# IMU_REV_E.net
KiCad netlist of a schematic drawn in Altium Designer
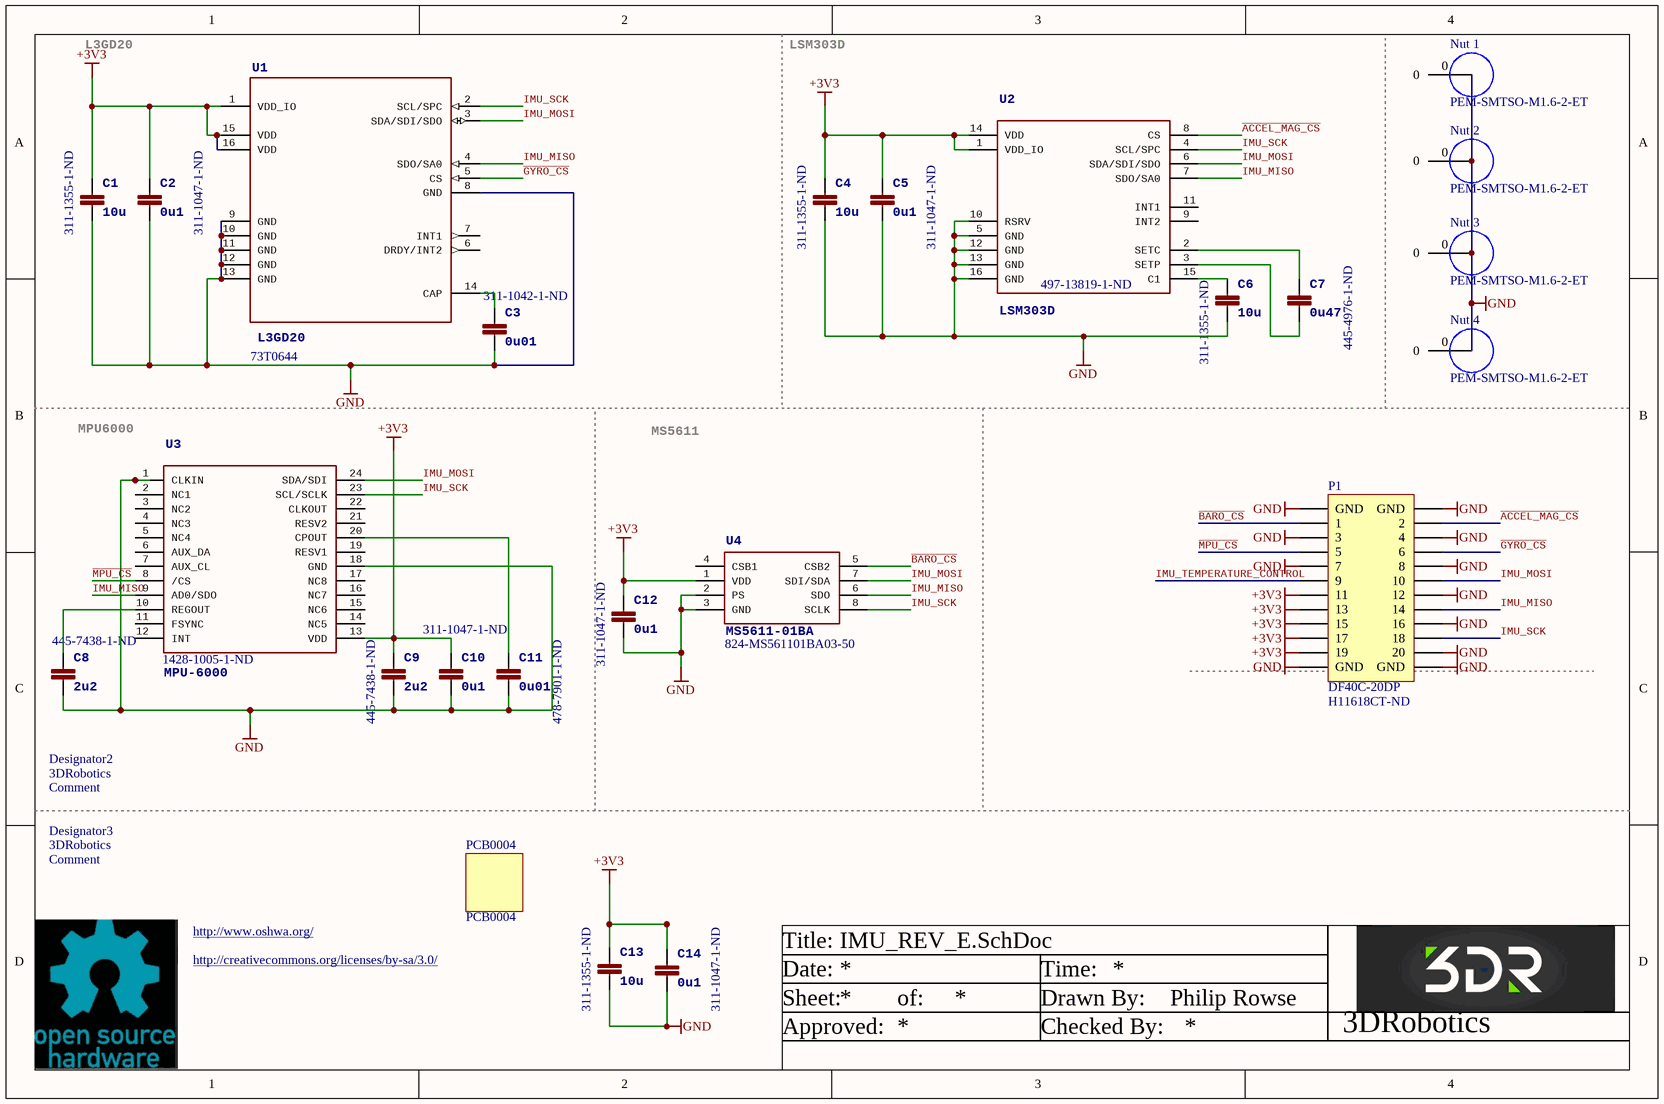
[diagram p0: IMU_REV_E.SchDoc]

(export (version "E")
  (design (tool "Eeschema 10.0.6"))
  (components
    (comp (ref "C1")
      (value "10u")
      (footprint "0805-CAP")
      (description "Capacitor, 10uF, 10V, Y5V, 0805, Ceramic")
      (fields
        (field (name "PARTNO") "CC0805ZKY5V6BB106")
        (field (name "SUPPLIER PART NUMBER 1") "311-1355-1-ND")
        (field (name "3DR_PARTNO") "ECM0713")
      )
      (libsource (lib "lib_pixhawk") (part "CAPACITOR-0805"))
    )
    (comp (ref "C2")
      (value "0u1")
      (footprint "0402-CAP")
      (description "Capacitor, 0.1uF, 16V, Y5V, 0402, Ceramic")
      (fields
        (field (name "PARTNO") "CC0402ZRY5V7BB104")
        (field (name "SUPPLIER PART NUMBER 1") "311-1047-1-ND")
        (field (name "3DR_PARTNO") "ECM0700")
      )
      (libsource (lib "lib_pixhawk") (part "CAPACITOR-0402"))
    )
    (comp (ref "C3")
      (value "0u01")
      (footprint "0402-CAP")
      (description "Capacitor, 10000pF, 16V, 10%, X7R, 0402, Ceramic")
      (fields
        (field (name "PARTNO") "CC0402KRX7R7BB103")
        (field (name "SUPPLIER PART NUMBER 1") "311-1042-1-ND")
        (field (name "3DR_PARTNO") "ECM0711")
      )
      (libsource (lib "lib_pixhawk") (part "CAPACITOR-0402"))
    )
    (comp (ref "C4")
      (value "10u")
      (footprint "0805-CAP")
      (description "Capacitor, 10uF, 10V, Y5V, 0805, Ceramic")
      (fields
        (field (name "PARTNO") "CC0805ZKY5V6BB106")
        (field (name "SUPPLIER PART NUMBER 1") "311-1355-1-ND")
        (field (name "3DR_PARTNO") "ECM0713")
      )
      (libsource (lib "lib_pixhawk") (part "CAPACITOR-0805"))
    )
    (comp (ref "C5")
      (value "0u1")
      (footprint "0402-CAP")
      (description "Capacitor, 0.1uF, 16V, Y5V, 0402, Ceramic")
      (fields
        (field (name "PARTNO") "CC0402ZRY5V7BB104")
        (field (name "SUPPLIER PART NUMBER 1") "311-1047-1-ND")
        (field (name "3DR_PARTNO") "ECM0700")
      )
      (libsource (lib "lib_pixhawk") (part "CAPACITOR-0402"))
    )
    (comp (ref "C6")
      (value "10u")
      (footprint "0805-CAP")
      (description "Capacitor, 10uF, 10V, Y5V, 0805, Ceramic")
      (fields
        (field (name "PARTNO") "CC0805ZKY5V6BB106")
        (field (name "SUPPLIER PART NUMBER 1") "311-1355-1-ND")
        (field (name "3DR_PARTNO") "ECM0713")
      )
      (libsource (lib "lib_pixhawk") (part "CAPACITOR-0805"))
    )
    (comp (ref "C7")
      (value "0u47")
      (footprint "0402-CAP")
      (description "Capacitor,  0.47uF, 16V, 10%, X5R, 0402, Ceramic")
      (fields
        (field (name "PARTNO") "C1005X5R1C474K050BC")
        (field (name "SUPPLIER PART NUMBER 1") "445-4976-1-ND")
        (field (name "3DR_PARTNO") "ECM0704")
      )
      (libsource (lib "lib_pixhawk") (part "CAPACITOR-0402"))
    )
    (comp (ref "C8")
      (value "2u2")
      (footprint "0603-CAP")
      (description "Capacitor, 2.2uF, 16V, 10%, X6S, 0603, Ceramic")
      (fields
        (field (name "PARTNO") "C1608X6S1C225K080AC")
        (field (name "SUPPLIER PART NUMBER 1") "445-7438-1-ND")
        (field (name "3DR_PARTNO") "ECM0619")
      )
      (libsource (lib "lib_pixhawk") (part "CAPACITOR-0603"))
    )
    (comp (ref "C9")
      (value "2u2")
      (footprint "0603-CAP")
      (description "Capacitor, 2.2uF, 16V, 10%, X6S, 0603, Ceramic")
      (fields
        (field (name "PARTNO") "C1608X6S1C225K080AC")
        (field (name "SUPPLIER PART NUMBER 1") "445-7438-1-ND")
        (field (name "3DR_PARTNO") "ECM0619")
      )
      (libsource (lib "lib_pixhawk") (part "CAPACITOR-0603"))
    )
    (comp (ref "C10")
      (value "0u1")
      (footprint "0402-CAP")
      (description "Capacitor, 0.1uF, 16V, Y5V, 0402, Ceramic")
      (fields
        (field (name "PARTNO") "CC0402ZRY5V7BB104")
        (field (name "SUPPLIER PART NUMBER 1") "311-1047-1-ND")
        (field (name "3DR_PARTNO") "ECM0700")
      )
      (libsource (lib "lib_pixhawk") (part "CAPACITOR-0402"))
    )
    (comp (ref "C11")
      (value "0u01")
      (footprint "0603-CAP")
      (description "Capacitor, 10000pF, 25V, 5%, X7R, 0603, Ceramic")
      (fields
        (field (name "PARTNO") "06033C103JAT2A")
        (field (name "SUPPLIER PART NUMBER 1") "478-7901-1-ND")
        (field (name "3DR_PARTNO") "ECM0620")
      )
      (libsource (lib "lib_pixhawk") (part "CAPACITOR-0603"))
    )
    (comp (ref "C12")
      (value "0u1")
      (footprint "0402-CAP")
      (description "Capacitor, 0.1uF, 16V, Y5V, 0402, Ceramic")
      (fields
        (field (name "PARTNO") "CC0402ZRY5V7BB104")
        (field (name "SUPPLIER PART NUMBER 1") "311-1047-1-ND")
        (field (name "3DR_PARTNO") "ECM0700")
      )
      (libsource (lib "lib_pixhawk") (part "CAPACITOR-0402"))
    )
    (comp (ref "C13")
      (value "10u")
      (footprint "0805-CAP")
      (description "Capacitor, 10uF, 10V, Y5V, 0805, Ceramic")
      (fields
        (field (name "PARTNO") "CC0805ZKY5V6BB106")
        (field (name "SUPPLIER PART NUMBER 1") "311-1355-1-ND")
        (field (name "3DR_PARTNO") "ECM0713")
      )
      (libsource (lib "lib_pixhawk") (part "CAPACITOR-0805"))
    )
    (comp (ref "C14")
      (value "0u1")
      (footprint "0402-CAP")
      (description "Capacitor, 0.1uF, 16V, Y5V, 0402, Ceramic")
      (fields
        (field (name "PARTNO") "CC0402ZRY5V7BB104")
        (field (name "SUPPLIER PART NUMBER 1") "311-1047-1-ND")
        (field (name "3DR_PARTNO") "ECM0700")
      )
      (libsource (lib "lib_pixhawk") (part "CAPACITOR-0402"))
    )
    (comp (ref "Designator2")
      (value "Comment")
      (footprint "3DR_SMALL")
      (fields (field (name "PARTNO") "DO NOT FIT"))
      (libsource (lib "lib_pixhawk") (part "3DR-Logo Large"))
    )
    (comp (ref "Designator3")
      (value "Comment")
      (footprint "3DR_SMALL")
      (fields (field (name "PARTNO") "DO NOT FIT"))
      (libsource (lib "lib_pixhawk") (part "3DR-Logo Large"))
    )
    (comp (ref "Nut 1")
      (value "PEM-SMTSO-M1.6-2-ET")
      (footprint "PEM-SMTSO-M1.6-2-ET")
      (description "Fastener, M1.6x2mm, SMTSO, Carbon Steel")
      (fields (field (name "3DR_PARTNO") "PRT0438"))
      (libsource (lib "pixhawk2") (part "PEM-SMTSO-M1.6-2-ET"))
    )
    (comp (ref "Nut 2")
      (value "PEM-SMTSO-M1.6-2-ET")
      (footprint "PEM-SMTSO-M1.6-2-ET")
      (description "Fastener, M1.6x2mm, SMTSO, Carbon Steel")
      (fields (field (name "3DR_PARTNO") "PRT0438"))
      (libsource (lib "pixhawk2") (part "PEM-SMTSO-M1.6-2-ET"))
    )
    (comp (ref "Nut 3")
      (value "PEM-SMTSO-M1.6-2-ET")
      (footprint "PEM-SMTSO-M1.6-2-ET")
      (description "Fastener, M1.6x2mm, SMTSO, Carbon Steel")
      (fields (field (name "3DR_PARTNO") "PRT0438"))
      (libsource (lib "pixhawk2") (part "PEM-SMTSO-M1.6-2-ET"))
    )
    (comp (ref "Nut 4")
      (value "PEM-SMTSO-M1.6-2-ET")
      (footprint "PEM-SMTSO-M1.6-2-ET")
      (description "Fastener, M1.6x2mm, SMTSO, Carbon Steel")
      (fields (field (name "3DR_PARTNO") "PRT0438"))
      (libsource (lib "pixhawk2") (part "PEM-SMTSO-M1.6-2-ET"))
    )
    (comp (ref "P1")
      (value "DF40C-20DP")
      (footprint "DF40C-20-DP")
      (description "Connector, HDR, 20Pos, 0.4mm, SMD, GOLD")
      (fields
        (field (name "SUPPLIER PART NUMBER 1") "H11618CT-ND")
        (field (name "3DR_PARTNO") "ECM0510")
        (field (name "PUBLISHER") "Altium Limited")
      )
      (libsource (lib "pixhawk2") (part "DF40C-20DP"))
    )
    (comp (ref "PCB0004")
      (value "PCB0004")
      (description "IMU PCB")
      (libsource (lib "lib_pixhawk") (part "PCB_0004"))
    )
    (comp (ref "U1")
      (value "L3GD20")
      (footprint "L3GD20")
      (description "Sensor, Low-power, Three-axis, Angular rate")
      (fields (field (name "SUPPLIER PART NUMBER 1") "73T0644") (field (name "3DR_PARTNO") "ECM0827"))
      (libsource (lib "pixhawk2") (part "L3GD20"))
    )
    (comp (ref "U2")
      (value "LSM303D")
      (footprint "LSM303D")
      (description "Module, 3D Accelerometer, 3D Magnetometer")
      (fields (field (name "SUPPLIER PART NUMBER 1") "497-13819-1-ND") (field (name "3DR_PARTNO") "ECM0828"))
      (libsource (lib "pixhawk2") (part "LSM303D"))
    )
    (comp (ref "U3")
      (value "MPU-6000")
      (footprint "QFN-24")
      (description "3 Axis Accel, 3Axis Gyro")
      (fields (field (name "SUPPLIER PART NUMBER 1") "1428-1005-1-ND") (field (name "3DR_PARTNO") "ECM0834"))
      (libsource (lib "pixhawk2") (part "MPU-6000"))
    )
    (comp (ref "U4")
      (value "MS5611-01BA")
      (footprint "MS5611-01BA")
      (description "Board, Digital pressure sensor I2C/SPI")
      (fields
        (field (name "SUPPLIER PART NUMBER 1") "824-MS561101BA03-50")
        (field (name "3DR_PARTNO") "ECM0835")
      )
      (libsource (lib "pixhawk2") (part "MS5611-01BA"))
    )
  )
  (nets
    (net (code "1") (name "+3V3") (class "Default")
      (node (ref "C1") (pin "P$1") (pinfunction "1_P$1") (pintype "passive"))
      (node (ref "C10") (pin "P$1") (pinfunction "1_P$1") (pintype "passive"))
      (node (ref "C12") (pin "P$1") (pinfunction "1_P$1") (pintype "passive"))
      (node (ref "C13") (pin "P$1") (pinfunction "1_P$1") (pintype "passive"))
      (node (ref "C14") (pin "P$1") (pinfunction "1_P$1") (pintype "passive"))
      (node (ref "C2") (pin "P$1") (pinfunction "1_P$1") (pintype "passive"))
      (node (ref "C4") (pin "P$1") (pinfunction "1_P$1") (pintype "passive"))
      (node (ref "C5") (pin "P$1") (pinfunction "1_P$1") (pintype "passive"))
      (node (ref "C9") (pin "P$1") (pinfunction "1_P$1") (pintype "passive"))
      (node (ref "P1") (pin "11") (pinfunction "11_11") (pintype "passive"))
      (node (ref "P1") (pin "13") (pinfunction "13_13") (pintype "passive"))
      (node (ref "P1") (pin "15") (pinfunction "15_15") (pintype "passive"))
      (node (ref "P1") (pin "17") (pinfunction "17_17") (pintype "passive"))
      (node (ref "P1") (pin "19") (pinfunction "19_19") (pintype "passive"))
      (node (ref "U1") (pin "1") (pinfunction "VDD_IO_1") (pintype "power_in"))
      (node (ref "U1") (pin "15") (pinfunction "VDD_15") (pintype "power_in"))
      (node (ref "U1") (pin "16") (pinfunction "VDD_16") (pintype "power_in"))
      (node (ref "U2") (pin "1") (pinfunction "VDD_IO_1") (pintype "passive"))
      (node (ref "U2") (pin "14") (pinfunction "VDD_14") (pintype "passive"))
      (node (ref "U3") (pin "13") (pinfunction "VDD_13") (pintype "passive"))
      (node (ref "U4") (pin "1") (pinfunction "VDD_1") (pintype "passive"))
    )
    (net (code "2") (name "/IMU_MISO") (class "Default")
      (node (ref "P1") (pin "14") (pinfunction "14_14") (pintype "passive"))
      (node (ref "U1") (pin "4") (pinfunction "SDO/SA0_4") (pintype "input"))
      (node (ref "U2") (pin "7") (pinfunction "SDO/SA0_7") (pintype "passive"))
      (node (ref "U3") (pin "9") (pinfunction "AD0/SDO_9") (pintype "passive"))
      (node (ref "U4") (pin "6") (pinfunction "SDO_6") (pintype "passive"))
    )
    (net (code "3") (name "/IMU_MOSI") (class "Default")
      (node (ref "P1") (pin "10") (pinfunction "10_10") (pintype "passive"))
      (node (ref "U1") (pin "3") (pinfunction "SDA/SDI/SDO_3") (pintype "bidirectional"))
      (node (ref "U2") (pin "6") (pinfunction "SDA/SDI/SDO_6") (pintype "passive"))
      (node (ref "U3") (pin "24") (pinfunction "SDA/SDI_24") (pintype "passive"))
      (node (ref "U4") (pin "7") (pinfunction "SDI/SDA_7") (pintype "passive"))
    )
    (net (code "4") (name "/IMU_SCK") (class "Default")
      (node (ref "P1") (pin "18") (pinfunction "18_18") (pintype "passive"))
      (node (ref "U1") (pin "2") (pinfunction "SCL/SPC_2") (pintype "input"))
      (node (ref "U2") (pin "4") (pinfunction "SCL/SPC_4") (pintype "passive"))
      (node (ref "U3") (pin "23") (pinfunction "SCL/SCLK_23") (pintype "passive"))
      (node (ref "U4") (pin "8") (pinfunction "SCLK_8") (pintype "passive"))
    )
    (net (code "5") (name "/IMU_TEMPERATURE_CONTROL") (class "Default")
      (node (ref "P1") (pin "9") (pinfunction "9_9") (pintype "passive"))
    )
    (net (code "6") (name "/~{ACCEL_MAG_CS}") (class "Default")
      (node (ref "P1") (pin "2") (pinfunction "2_2") (pintype "passive"))
      (node (ref "U2") (pin "8") (pinfunction "CS_8") (pintype "passive"))
    )
    (net (code "7") (name "/~{BARO_CS}") (class "Default")
      (node (ref "P1") (pin "1") (pinfunction "1_1") (pintype "passive"))
      (node (ref "U4") (pin "5") (pinfunction "CSB2_5") (pintype "passive"))
    )
    (net (code "8") (name "/~{GYRO_CS}") (class "Default")
      (node (ref "P1") (pin "6") (pinfunction "6_6") (pintype "passive"))
      (node (ref "U1") (pin "5") (pinfunction "CS_5") (pintype "input"))
    )
    (net (code "9") (name "/~{MPU_CS}") (class "Default")
      (node (ref "P1") (pin "5") (pinfunction "5_5") (pintype "passive"))
      (node (ref "U3") (pin "8") (pinfunction "/CS_8") (pintype "passive"))
    )
    (net (code "10") (name "GND") (class "Default")
      (node (ref "C1") (pin "P$2") (pinfunction "2_P$2") (pintype "passive"))
      (node (ref "C10") (pin "P$2") (pinfunction "2_P$2") (pintype "passive"))
      (node (ref "C11") (pin "P$2") (pinfunction "2_P$2") (pintype "passive"))
      (node (ref "C12") (pin "P$2") (pinfunction "2_P$2") (pintype "passive"))
      (node (ref "C13") (pin "P$2") (pinfunction "2_P$2") (pintype "passive"))
      (node (ref "C14") (pin "P$2") (pinfunction "2_P$2") (pintype "passive"))
      (node (ref "C2") (pin "P$2") (pinfunction "2_P$2") (pintype "passive"))
      (node (ref "C3") (pin "P$2") (pinfunction "2_P$2") (pintype "passive"))
      (node (ref "C4") (pin "P$2") (pinfunction "2_P$2") (pintype "passive"))
      (node (ref "C5") (pin "P$2") (pinfunction "2_P$2") (pintype "passive"))
      (node (ref "C6") (pin "P$2") (pinfunction "2_P$2") (pintype "passive"))
      (node (ref "C8") (pin "P$2") (pinfunction "2_P$2") (pintype "passive"))
      (node (ref "C9") (pin "P$2") (pinfunction "2_P$2") (pintype "passive"))
      (node (ref "Nut 1") (pin "0") (pinfunction "0_0") (pintype "passive"))
      (node (ref "Nut 2") (pin "0") (pinfunction "0_0") (pintype "passive"))
      (node (ref "Nut 3") (pin "0") (pinfunction "0_0") (pintype "passive"))
      (node (ref "Nut 4") (pin "0") (pinfunction "0_0") (pintype "passive"))
      (node (ref "P1") (pin "12") (pinfunction "12_12") (pintype "passive"))
      (node (ref "P1") (pin "16") (pinfunction "16_16") (pintype "passive"))
      (node (ref "P1") (pin "20") (pinfunction "20_20") (pintype "passive"))
      (node (ref "P1") (pin "21") (pinfunction "GND_21") (pintype "passive"))
      (node (ref "P1") (pin "22") (pinfunction "GND_22") (pintype "passive"))
      (node (ref "P1") (pin "23") (pinfunction "GND_23") (pintype "passive"))
      (node (ref "P1") (pin "24") (pinfunction "GND_24") (pintype "passive"))
      (node (ref "P1") (pin "3") (pinfunction "3_3") (pintype "passive"))
      (node (ref "P1") (pin "4") (pinfunction "4_4") (pintype "passive"))
      (node (ref "P1") (pin "7") (pinfunction "7_7") (pintype "passive"))
      (node (ref "P1") (pin "8") (pinfunction "8_8") (pintype "passive"))
      (node (ref "U1") (pin "10") (pinfunction "GND_10") (pintype "power_in"))
      (node (ref "U1") (pin "11") (pinfunction "GND_11") (pintype "power_in"))
      (node (ref "U1") (pin "12") (pinfunction "GND_12") (pintype "power_in"))
      (node (ref "U1") (pin "13") (pinfunction "GND_13") (pintype "power_in"))
      (node (ref "U1") (pin "8") (pinfunction "GND_8") (pintype "power_in"))
      (node (ref "U1") (pin "9") (pinfunction "GND_9") (pintype "power_in"))
      (node (ref "U2") (pin "10") (pinfunction "RSRV_10") (pintype "passive"))
      (node (ref "U2") (pin "12") (pinfunction "GND_12") (pintype "passive"))
      (node (ref "U2") (pin "13") (pinfunction "GND_13") (pintype "passive"))
      (node (ref "U2") (pin "16") (pinfunction "GND_16") (pintype "passive"))
      (node (ref "U2") (pin "5") (pinfunction "GND_5") (pintype "passive"))
      (node (ref "U3") (pin "1") (pinfunction "CLKIN_1") (pintype "passive"))
      (node (ref "U3") (pin "18") (pinfunction "GND_18") (pintype "passive"))
      (node (ref "U4") (pin "2") (pinfunction "PS_2") (pintype "passive"))
      (node (ref "U4") (pin "3") (pinfunction "GND_3") (pintype "passive"))
    )
    (net (code "11") (name "Net-(C3-1)") (class "Default")
      (node (ref "C3") (pin "P$1") (pinfunction "1_P$1") (pintype "passive"))
      (node (ref "U1") (pin "14") (pinfunction "CAP_14") (pintype "passive"))
    )
    (net (code "12") (name "Net-(C6-1)") (class "Default")
      (node (ref "C6") (pin "P$1") (pinfunction "1_P$1") (pintype "passive"))
      (node (ref "U2") (pin "15") (pinfunction "C1_15") (pintype "passive"))
    )
    (net (code "13") (name "Net-(C7-1)") (class "Default")
      (node (ref "C7") (pin "P$1") (pinfunction "1_P$1") (pintype "passive"))
      (node (ref "U2") (pin "2") (pinfunction "SETC_2") (pintype "passive"))
    )
    (net (code "14") (name "Net-(C7-2)") (class "Default")
      (node (ref "C7") (pin "P$2") (pinfunction "2_P$2") (pintype "passive"))
      (node (ref "U2") (pin "3") (pinfunction "SETP_3") (pintype "passive"))
    )
    (net (code "15") (name "Net-(C8-1)") (class "Default")
      (node (ref "C8") (pin "P$1") (pinfunction "1_P$1") (pintype "passive"))
      (node (ref "U3") (pin "10") (pinfunction "REGOUT_10") (pintype "passive"))
    )
    (net (code "16") (name "Net-(C11-1)") (class "Default")
      (node (ref "C11") (pin "P$1") (pinfunction "1_P$1") (pintype "passive"))
      (node (ref "U3") (pin "20") (pinfunction "CPOUT_20") (pintype "passive"))
    )
    (net (code "17") (name "unconnected-(U1-DRDY{slash}INT2-Pad6)") (class "Default")
      (node (ref "U1") (pin "6") (pinfunction "DRDY/INT2_6") (pintype "output"))
    )
    (net (code "18") (name "unconnected-(U1-INT1-Pad7)") (class "Default")
      (node (ref "U1") (pin "7") (pinfunction "INT1_7") (pintype "output"))
    )
    (net (code "19") (name "unconnected-(U2-INT1-Pad11)") (class "Default")
      (node (ref "U2") (pin "11") (pinfunction "INT1_11") (pintype "passive"))
    )
    (net (code "20") (name "unconnected-(U2-INT2-Pad9)") (class "Default")
      (node (ref "U2") (pin "9") (pinfunction "INT2_9") (pintype "passive"))
    )
    (net (code "21") (name "unconnected-(U3-AUX_CL-Pad7)") (class "Default")
      (node (ref "U3") (pin "7") (pinfunction "AUX_CL_7") (pintype "passive"))
    )
    (net (code "22") (name "unconnected-(U3-AUX_DA-Pad6)") (class "Default")
      (node (ref "U3") (pin "6") (pinfunction "AUX_DA_6") (pintype "passive"))
    )
    (net (code "23") (name "unconnected-(U3-CLKOUT-Pad22)") (class "Default")
      (node (ref "U3") (pin "22") (pinfunction "CLKOUT_22") (pintype "passive"))
    )
    (net (code "24") (name "unconnected-(U3-FSYNC-Pad11)") (class "Default")
      (node (ref "U3") (pin "11") (pinfunction "FSYNC_11") (pintype "passive"))
    )
    (net (code "25") (name "unconnected-(U3-INT-Pad12)") (class "Default")
      (node (ref "U3") (pin "12") (pinfunction "INT_12") (pintype "passive"))
    )
    (net (code "26") (name "unconnected-(U3-NC1-Pad2)") (class "Default")
      (node (ref "U3") (pin "2") (pinfunction "NC1_2") (pintype "passive"))
    )
    (net (code "27") (name "unconnected-(U3-NC2-Pad3)") (class "Default")
      (node (ref "U3") (pin "3") (pinfunction "NC2_3") (pintype "passive"))
    )
    (net (code "28") (name "unconnected-(U3-NC3-Pad4)") (class "Default")
      (node (ref "U3") (pin "4") (pinfunction "NC3_4") (pintype "passive"))
    )
    (net (code "29") (name "unconnected-(U3-NC4-Pad5)") (class "Default")
      (node (ref "U3") (pin "5") (pinfunction "NC4_5") (pintype "passive"))
    )
    (net (code "30") (name "unconnected-(U3-NC5-Pad14)") (class "Default")
      (node (ref "U3") (pin "14") (pinfunction "NC5_14") (pintype "passive"))
    )
    (net (code "31") (name "unconnected-(U3-NC6-Pad15)") (class "Default")
      (node (ref "U3") (pin "15") (pinfunction "NC6_15") (pintype "passive"))
    )
    (net (code "32") (name "unconnected-(U3-NC7-Pad16)") (class "Default")
      (node (ref "U3") (pin "16") (pinfunction "NC7_16") (pintype "passive"))
    )
    (net (code "33") (name "unconnected-(U3-NC8-Pad17)") (class "Default")
      (node (ref "U3") (pin "17") (pinfunction "NC8_17") (pintype "passive"))
    )
    (net (code "34") (name "unconnected-(U3-RESV1-Pad19)") (class "Default")
      (node (ref "U3") (pin "19") (pinfunction "RESV1_19") (pintype "passive"))
    )
    (net (code "35") (name "unconnected-(U3-RESV2-Pad21)") (class "Default")
      (node (ref "U3") (pin "21") (pinfunction "RESV2_21") (pintype "passive"))
    )
    (net (code "36") (name "unconnected-(U4-CSB1-Pad4)") (class "Default")
      (node (ref "U4") (pin "4") (pinfunction "CSB1_4") (pintype "passive"))
    )
  )
)
